# cc2652_zr_Type-A.net
KiCad netlist of a schematic drawn in EAGLE
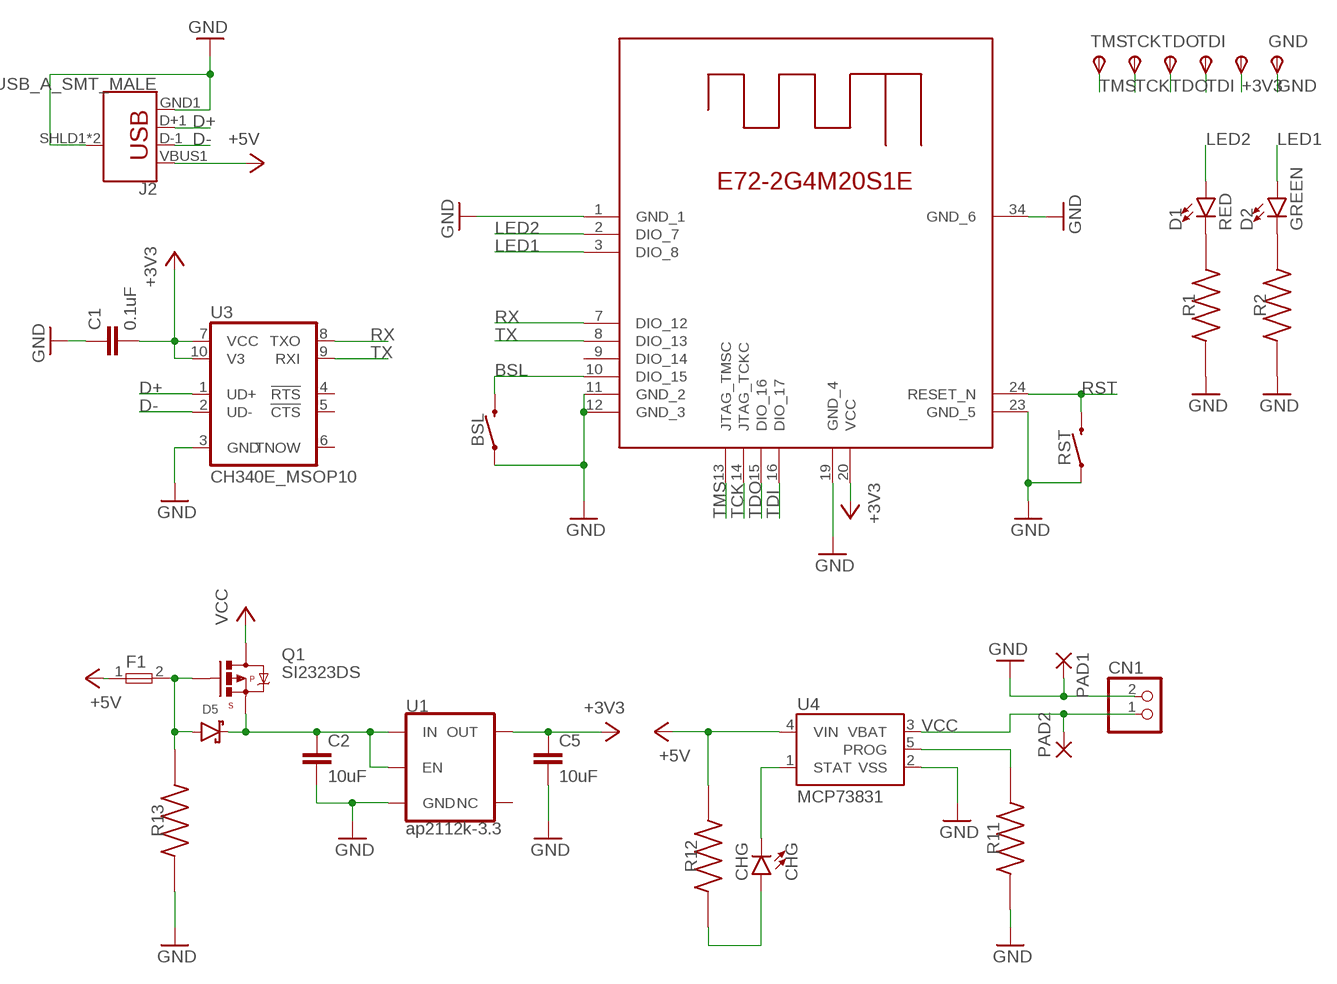
[diagram p0: schematic, sheet 1]

(export (version "E")
  (design (tool "Eeschema 10.0.6"))
  (components
    (comp (ref "+3V3")
      (value "TPSTP11R")
      (footprint "eagle-import:TP11R")
      (libsource (lib "eagle-import") (part "TPSTP11R"))
    )
    (comp (ref "BSL")
      (value "MOMENTARY-SWITCH-SPST-SMD-4.6X2.8MM")
      (footprint "eagle-import:TACTILE_SWITCH_SMD_4.6X2.8MM")
      (libsource (lib "eagle-import") (part "MOMENTARY-SWITCH-SPST-SMD-4.6X2.8MM"))
    )
    (comp (ref "C1")
      (value "0.1uF")
      (footprint "eagle-import:0603")
      (libsource (lib "eagle-import") (part "0.1UF-0603-25V-(+80/-20%)"))
    )
    (comp (ref "C2")
      (value "10uF")
      (footprint "eagle-import:0603")
      (libsource (lib "eagle-import") (part "10UF-0603-6.3V-20%"))
    )
    (comp (ref "C5")
      (value "10uF")
      (footprint "eagle-import:0603")
      (libsource (lib "eagle-import") (part "10UF-0603-6.3V-20%"))
    )
    (comp (ref "CHG")
      (value "CHG")
      (footprint "eagle-import:LED-0603")
      (libsource (lib "eagle-import") (part "LED-BLUE0603"))
    )
    (comp (ref "CN1")
      (value "JST_2PIN-SMT-RA")
      (footprint "eagle-import:JST-PH-2-SMT-RA")
      (libsource (lib "eagle-import") (part "JST_2PIN-SMT-RA"))
    )
    (comp (ref "D1")
      (value "RED")
      (footprint "eagle-import:LED-0603")
      (libsource (lib "eagle-import") (part "LED-RED0603"))
    )
    (comp (ref "D2")
      (value "GREEN")
      (footprint "eagle-import:LED-0603")
      (libsource (lib "eagle-import") (part "LED-GREEN0603"))
    )
    (comp (ref "D5")
      (value "DIODE-SCHOTTKY")
      (footprint "eagle-import:SOD-323")
      (libsource (lib "eagle-import") (part "DIODE-SCHOTTKY"))
    )
    (comp (ref "F1")
      (value "FEMTOSMDC016F-02")
      (footprint "eagle-import:RESC1608X50N")
      (fields (field (name "MF") "Littelfuse Inc."))
      (libsource (lib "eagle-import") (part "FEMTOSMDC016F-02"))
    )
    (comp (ref "GND")
      (value "TPSTP11R")
      (footprint "eagle-import:TP11R")
      (libsource (lib "eagle-import") (part "TPSTP11R"))
    )
    (comp (ref "J2")
      (value "USB_A_SMT_MALE")
      (footprint "eagle-import:USB-A-SMT-MALE")
      (libsource (lib "eagle-import") (part "USB_A_SMT_MALE"))
    )
    (comp (ref "PAD1")
      (value "WIREPADSMD1,27-254")
      (footprint "eagle-import:SMD1,27-2,54")
      (libsource (lib "eagle-import") (part "WIREPADSMD1,27-254"))
    )
    (comp (ref "PAD2")
      (value "WIREPADSMD1,27-254")
      (footprint "eagle-import:SMD1,27-2,54")
      (libsource (lib "eagle-import") (part "WIREPADSMD1,27-254"))
    )
    (comp (ref "Q1")
      (value "SI2323DS")
      (footprint "eagle-import:SOT23")
      (libsource (lib "eagle-import") (part "MOSFET-PCHANNEL"))
    )
    (comp (ref "R1")
      (value "2.2k")
      (footprint "eagle-import:RESC1005X40N")
      (fields (field (name "MF") "Yageo") (field (name "MP") "RC0402FR-073M6L"))
      (libsource (lib "eagle-import") (part "RC0402FR-073M6L"))
    )
    (comp (ref "R2")
      (value "2.2k")
      (footprint "eagle-import:RESC1005X40N")
      (fields (field (name "MF") "Yageo") (field (name "MP") "RC0402FR-073M6L"))
      (libsource (lib "eagle-import") (part "RC0402FR-073M6L"))
    )
    (comp (ref "R11")
      (value "2k")
      (footprint "eagle-import:RESC1005X40N")
      (fields (field (name "MF") "Yageo") (field (name "MP") "RC0402FR-073M6L"))
      (libsource (lib "eagle-import") (part "RC0402FR-073M6L"))
    )
    (comp (ref "R12")
      (value "2.2k")
      (footprint "eagle-import:RESC1005X40N")
      (fields (field (name "MF") "Yageo") (field (name "MP") "RC0402FR-073M6L"))
      (libsource (lib "eagle-import") (part "RC0402FR-073M6L"))
    )
    (comp (ref "R13")
      (value "10k")
      (footprint "eagle-import:RESC1005X40N")
      (fields (field (name "MF") "Yageo") (field (name "MP") "RC0402FR-073M6L"))
      (libsource (lib "eagle-import") (part "RC0402FR-073M6L"))
    )
    (comp (ref "RST")
      (value "MOMENTARY-SWITCH-SPST-SMD-4.6X2.8MM")
      (footprint "eagle-import:TACTILE_SWITCH_SMD_4.6X2.8MM")
      (libsource (lib "eagle-import") (part "MOMENTARY-SWITCH-SPST-SMD-4.6X2.8MM"))
    )
    (comp (ref "TCK")
      (value "TPSTP11R")
      (footprint "eagle-import:TP11R")
      (libsource (lib "eagle-import") (part "TPSTP11R"))
    )
    (comp (ref "TDI")
      (value "TPSTP11R")
      (footprint "eagle-import:TP11R")
      (libsource (lib "eagle-import") (part "TPSTP11R"))
    )
    (comp (ref "TDO")
      (value "TPSTP11R")
      (footprint "eagle-import:TP11R")
      (libsource (lib "eagle-import") (part "TPSTP11R"))
    )
    (comp (ref "TMS")
      (value "TPSTP11R")
      (footprint "eagle-import:TP11R")
      (libsource (lib "eagle-import") (part "TPSTP11R"))
    )
    (comp (ref "U$1")
      (value "E72-2G4M20S1E")
      (footprint "eagle-import:E72-2G4M20S1E")
      (libsource (lib "eagle-import") (part "E72-2G4M20S1E"))
    )
    (comp (ref "U1")
      (value "ap2112k-3.3")
      (footprint "eagle-import:SOT23-5")
      (libsource (lib "eagle-import") (part "V_REG_AP2112K-3.3V"))
    )
    (comp (ref "U3")
      (value "CH340E_MSOP10")
      (footprint "eagle-import:MSOP10")
      (fields (field (name "MF") "WCH") (field (name "MP") "CH340E"))
      (libsource (lib "eagle-import") (part "CH340E_MSOP10"))
    )
    (comp (ref "U4")
      (value "MCP73831")
      (footprint "eagle-import:SOT23-5")
      (libsource (lib "eagle-import") (part "MCP73831"))
    )
  )
  (nets
    (net (code "1") (name "+3V3") (class "Default")
      (node (ref "+3V3") (pin "TP") (pinfunction "PP_TP") (pintype "input"))
      (node (ref "C1") (pin "2") (pinfunction "2_2") (pintype "passive"))
      (node (ref "C5") (pin "1") (pinfunction "1_1") (pintype "passive"))
      (node (ref "U$1") (pin "20") (pinfunction "VCC_20") (pintype "bidirectional"))
      (node (ref "U1") (pin "5") (pinfunction "OUT_5") (pintype "passive"))
      (node (ref "U3") (pin "10") (pinfunction "V3_10") (pintype "bidirectional"))
      (node (ref "U3") (pin "7") (pinfunction "VCC_7") (pintype "bidirectional"))
    )
    (net (code "2") (name "+5V") (class "Default")
      (node (ref "F1") (pin "1") (pinfunction "1_1") (pintype "passive"))
      (node (ref "J2") (pin "VBUS1") (pinfunction "VBUS_VBUS1") (pintype "power_in"))
      (node (ref "R12") (pin "2") (pinfunction "2_2") (pintype "passive"))
      (node (ref "U4") (pin "4") (pinfunction "VIN_4") (pintype "power_in"))
    )
    (net (code "3") (name "/BSL") (class "Default")
      (node (ref "BSL") (pin "3") (pinfunction "2_3") (pintype "passive"))
      (node (ref "BSL") (pin "4") (pinfunction "2_4") (pintype "passive"))
      (node (ref "U$1") (pin "10") (pinfunction "DIO_15_10") (pintype "bidirectional"))
    )
    (net (code "4") (name "/D+") (class "Default")
      (node (ref "J2") (pin "D+1") (pinfunction "D+_D+1") (pintype "bidirectional"))
      (node (ref "U3") (pin "1") (pinfunction "UD+_1") (pintype "bidirectional"))
    )
    (net (code "5") (name "/D-") (class "Default")
      (node (ref "J2") (pin "D-1") (pinfunction "D-_D-1") (pintype "bidirectional"))
      (node (ref "U3") (pin "2") (pinfunction "UD-_2") (pintype "bidirectional"))
    )
    (net (code "6") (name "/LED1") (class "Default")
      (node (ref "D2") (pin "A") (pinfunction "A_A") (pintype "passive"))
      (node (ref "U$1") (pin "3") (pinfunction "DIO_8_3") (pintype "bidirectional"))
    )
    (net (code "7") (name "/LED2") (class "Default")
      (node (ref "D1") (pin "A") (pinfunction "A_A") (pintype "passive"))
      (node (ref "U$1") (pin "2") (pinfunction "DIO_7_2") (pintype "bidirectional"))
    )
    (net (code "8") (name "/RST") (class "Default")
      (node (ref "RST") (pin "3") (pinfunction "2_3") (pintype "passive"))
      (node (ref "RST") (pin "4") (pinfunction "2_4") (pintype "passive"))
      (node (ref "U$1") (pin "24") (pinfunction "RESET_N_24") (pintype "bidirectional"))
    )
    (net (code "9") (name "/RX") (class "Default")
      (node (ref "U$1") (pin "7") (pinfunction "DIO_12_7") (pintype "bidirectional"))
      (node (ref "U3") (pin "8") (pinfunction "TXO_8") (pintype "bidirectional"))
    )
    (net (code "10") (name "/TCK") (class "Default")
      (node (ref "TCK") (pin "TP") (pinfunction "PP_TP") (pintype "input"))
      (node (ref "U$1") (pin "14") (pinfunction "JTAG_TCKC_14") (pintype "bidirectional"))
    )
    (net (code "11") (name "/TDI") (class "Default")
      (node (ref "TDI") (pin "TP") (pinfunction "PP_TP") (pintype "input"))
      (node (ref "U$1") (pin "16") (pinfunction "DIO_17_16") (pintype "bidirectional"))
    )
    (net (code "12") (name "/TDO") (class "Default")
      (node (ref "TDO") (pin "TP") (pinfunction "PP_TP") (pintype "input"))
      (node (ref "U$1") (pin "15") (pinfunction "DIO_16_15") (pintype "bidirectional"))
    )
    (net (code "13") (name "/TMS") (class "Default")
      (node (ref "TMS") (pin "TP") (pinfunction "PP_TP") (pintype "input"))
      (node (ref "U$1") (pin "13") (pinfunction "JTAG_TMSC_13") (pintype "bidirectional"))
    )
    (net (code "14") (name "/TX") (class "Default")
      (node (ref "U$1") (pin "8") (pinfunction "DIO_13_8") (pintype "bidirectional"))
      (node (ref "U3") (pin "9") (pinfunction "RXI_9") (pintype "bidirectional"))
    )
    (net (code "15") (name "GND") (class "Default")
      (node (ref "BSL") (pin "1") (pinfunction "1_1") (pintype "passive"))
      (node (ref "BSL") (pin "2") (pinfunction "1_2") (pintype "passive"))
      (node (ref "C1") (pin "1") (pinfunction "1_1") (pintype "passive"))
      (node (ref "C2") (pin "2") (pinfunction "2_2") (pintype "passive"))
      (node (ref "C5") (pin "2") (pinfunction "2_2") (pintype "passive"))
      (node (ref "CN1") (pin "2") (pinfunction "1_2") (pintype "passive"))
      (node (ref "GND") (pin "TP") (pinfunction "PP_TP") (pintype "input"))
      (node (ref "J2") (pin "GND1") (pinfunction "GND_GND1") (pintype "power_in"))
      (node (ref "J2") (pin "SHLD1") (pinfunction "SHIELD_SHLD1") (pintype "bidirectional"))
      (node (ref "J2") (pin "SHLD2") (pinfunction "SHIELD_SHLD2") (pintype "bidirectional"))
      (node (ref "PAD1") (pin "1") (pinfunction "P_1") (pintype "passive"))
      (node (ref "R1") (pin "1") (pinfunction "1_1") (pintype "passive"))
      (node (ref "R11") (pin "1") (pinfunction "1_1") (pintype "passive"))
      (node (ref "R13") (pin "1") (pinfunction "1_1") (pintype "passive"))
      (node (ref "R2") (pin "1") (pinfunction "1_1") (pintype "passive"))
      (node (ref "RST") (pin "1") (pinfunction "1_1") (pintype "passive"))
      (node (ref "RST") (pin "2") (pinfunction "1_2") (pintype "passive"))
      (node (ref "U$1") (pin "1") (pinfunction "GND_1_1") (pintype "bidirectional"))
      (node (ref "U$1") (pin "11") (pinfunction "GND_2_11") (pintype "bidirectional"))
      (node (ref "U$1") (pin "12") (pinfunction "GND_3_12") (pintype "bidirectional"))
      (node (ref "U$1") (pin "19") (pinfunction "GND_4_19") (pintype "bidirectional"))
      (node (ref "U$1") (pin "23") (pinfunction "GND_5_23") (pintype "bidirectional"))
      (node (ref "U$1") (pin "34") (pinfunction "GND_6_34") (pintype "bidirectional"))
      (node (ref "U1") (pin "2") (pinfunction "GND_2") (pintype "input"))
      (node (ref "U3") (pin "3") (pinfunction "GND_3") (pintype "bidirectional"))
      (node (ref "U4") (pin "2") (pinfunction "VSS_2") (pintype "power_in"))
    )
    (net (code "16") (name "Net-(CHG-PadA)") (class "Default")
      (node (ref "CHG") (pin "A") (pinfunction "A_A") (pintype "passive"))
      (node (ref "R12") (pin "1") (pinfunction "1_1") (pintype "passive"))
    )
    (net (code "17") (name "Net-(D1-PadC)") (class "Default")
      (node (ref "D1") (pin "C") (pinfunction "C_C") (pintype "passive"))
      (node (ref "R1") (pin "2") (pinfunction "2_2") (pintype "passive"))
    )
    (net (code "18") (name "Net-(D2-PadC)") (class "Default")
      (node (ref "D2") (pin "C") (pinfunction "C_C") (pintype "passive"))
      (node (ref "R2") (pin "2") (pinfunction "2_2") (pintype "passive"))
    )
    (net (code "19") (name "Net-(Q1-G)") (class "Default")
      (node (ref "D5") (pin "A") (pinfunction "A_A") (pintype "passive"))
      (node (ref "F1") (pin "2") (pinfunction "2_2") (pintype "passive"))
      (node (ref "Q1") (pin "1") (pinfunction "G_1") (pintype "passive"))
      (node (ref "R13") (pin "2") (pinfunction "2_2") (pintype "passive"))
    )
    (net (code "20") (name "Net-(Q1-S)") (class "Default")
      (node (ref "C2") (pin "1") (pinfunction "1_1") (pintype "passive"))
      (node (ref "D5") (pin "C") (pinfunction "C_C") (pintype "passive"))
      (node (ref "Q1") (pin "2") (pinfunction "S_2") (pintype "passive"))
      (node (ref "U1") (pin "1") (pinfunction "IN_1") (pintype "input"))
      (node (ref "U1") (pin "3") (pinfunction "EN_3") (pintype "input"))
    )
    (net (code "21") (name "Net-(U4-PROG)") (class "Default")
      (node (ref "R11") (pin "2") (pinfunction "2_2") (pintype "passive"))
      (node (ref "U4") (pin "5") (pinfunction "PROG_5") (pintype "input"))
    )
    (net (code "22") (name "Net-(U4-STAT)") (class "Default")
      (node (ref "CHG") (pin "C") (pinfunction "C_C") (pintype "passive"))
      (node (ref "U4") (pin "1") (pinfunction "STAT_1") (pintype "output"))
    )
    (net (code "23") (name "VCC") (class "Default")
      (node (ref "CN1") (pin "1") (pinfunction "2_1") (pintype "passive"))
      (node (ref "PAD2") (pin "1") (pinfunction "P_1") (pintype "passive"))
      (node (ref "Q1") (pin "3") (pinfunction "D_3") (pintype "passive"))
      (node (ref "U4") (pin "3") (pinfunction "VBAT_3") (pintype "power_in"))
    )
    (net (code "24") (name "unconnected-(U$1-DIO_14-Pad9)") (class "Default")
      (node (ref "U$1") (pin "9") (pinfunction "DIO_14_9") (pintype "bidirectional"))
    )
    (net (code "25") (name "unconnected-(U1-NC-Pad4)") (class "Default")
      (node (ref "U1") (pin "4") (pinfunction "NC_4") (pintype "no_connect"))
    )
    (net (code "26") (name "unconnected-(U3-TNOW-Pad6)") (class "Default")
      (node (ref "U3") (pin "6") (pinfunction "TNOW_6") (pintype "bidirectional"))
    )
    (net (code "27") (name "unconnected-(U3-~{CTS}-Pad5)") (class "Default")
      (node (ref "U3") (pin "5") (pinfunction "~{CTS}_5") (pintype "bidirectional"))
    )
    (net (code "28") (name "unconnected-(U3-~{RTS}-Pad4)") (class "Default")
      (node (ref "U3") (pin "4") (pinfunction "~{RTS}_4") (pintype "bidirectional"))
    )
  )
)
